# teensy_4_x100.net
KiCad netlist of a schematic drawn in EAGLE
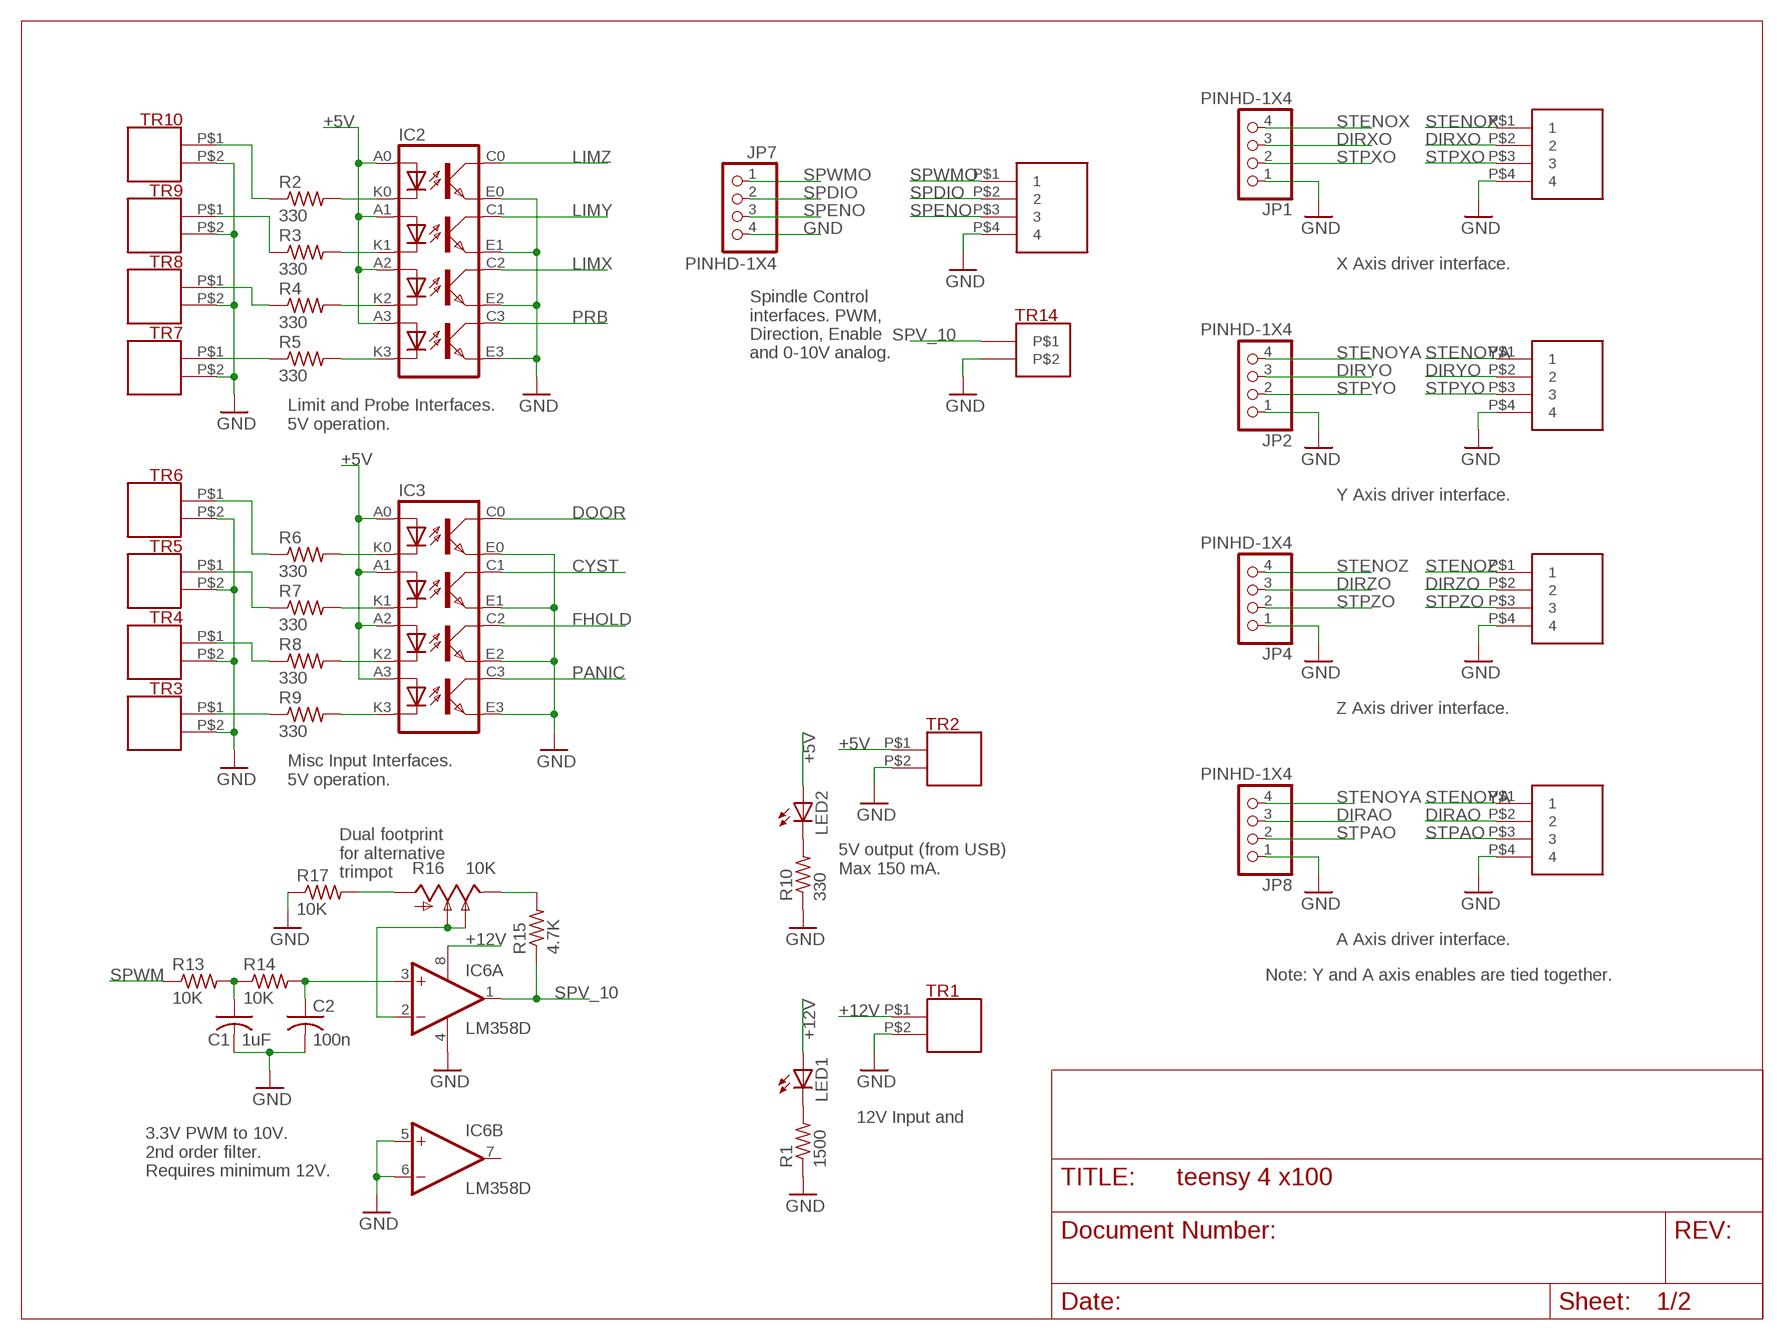
[diagram p0: schematic, sheet 1]
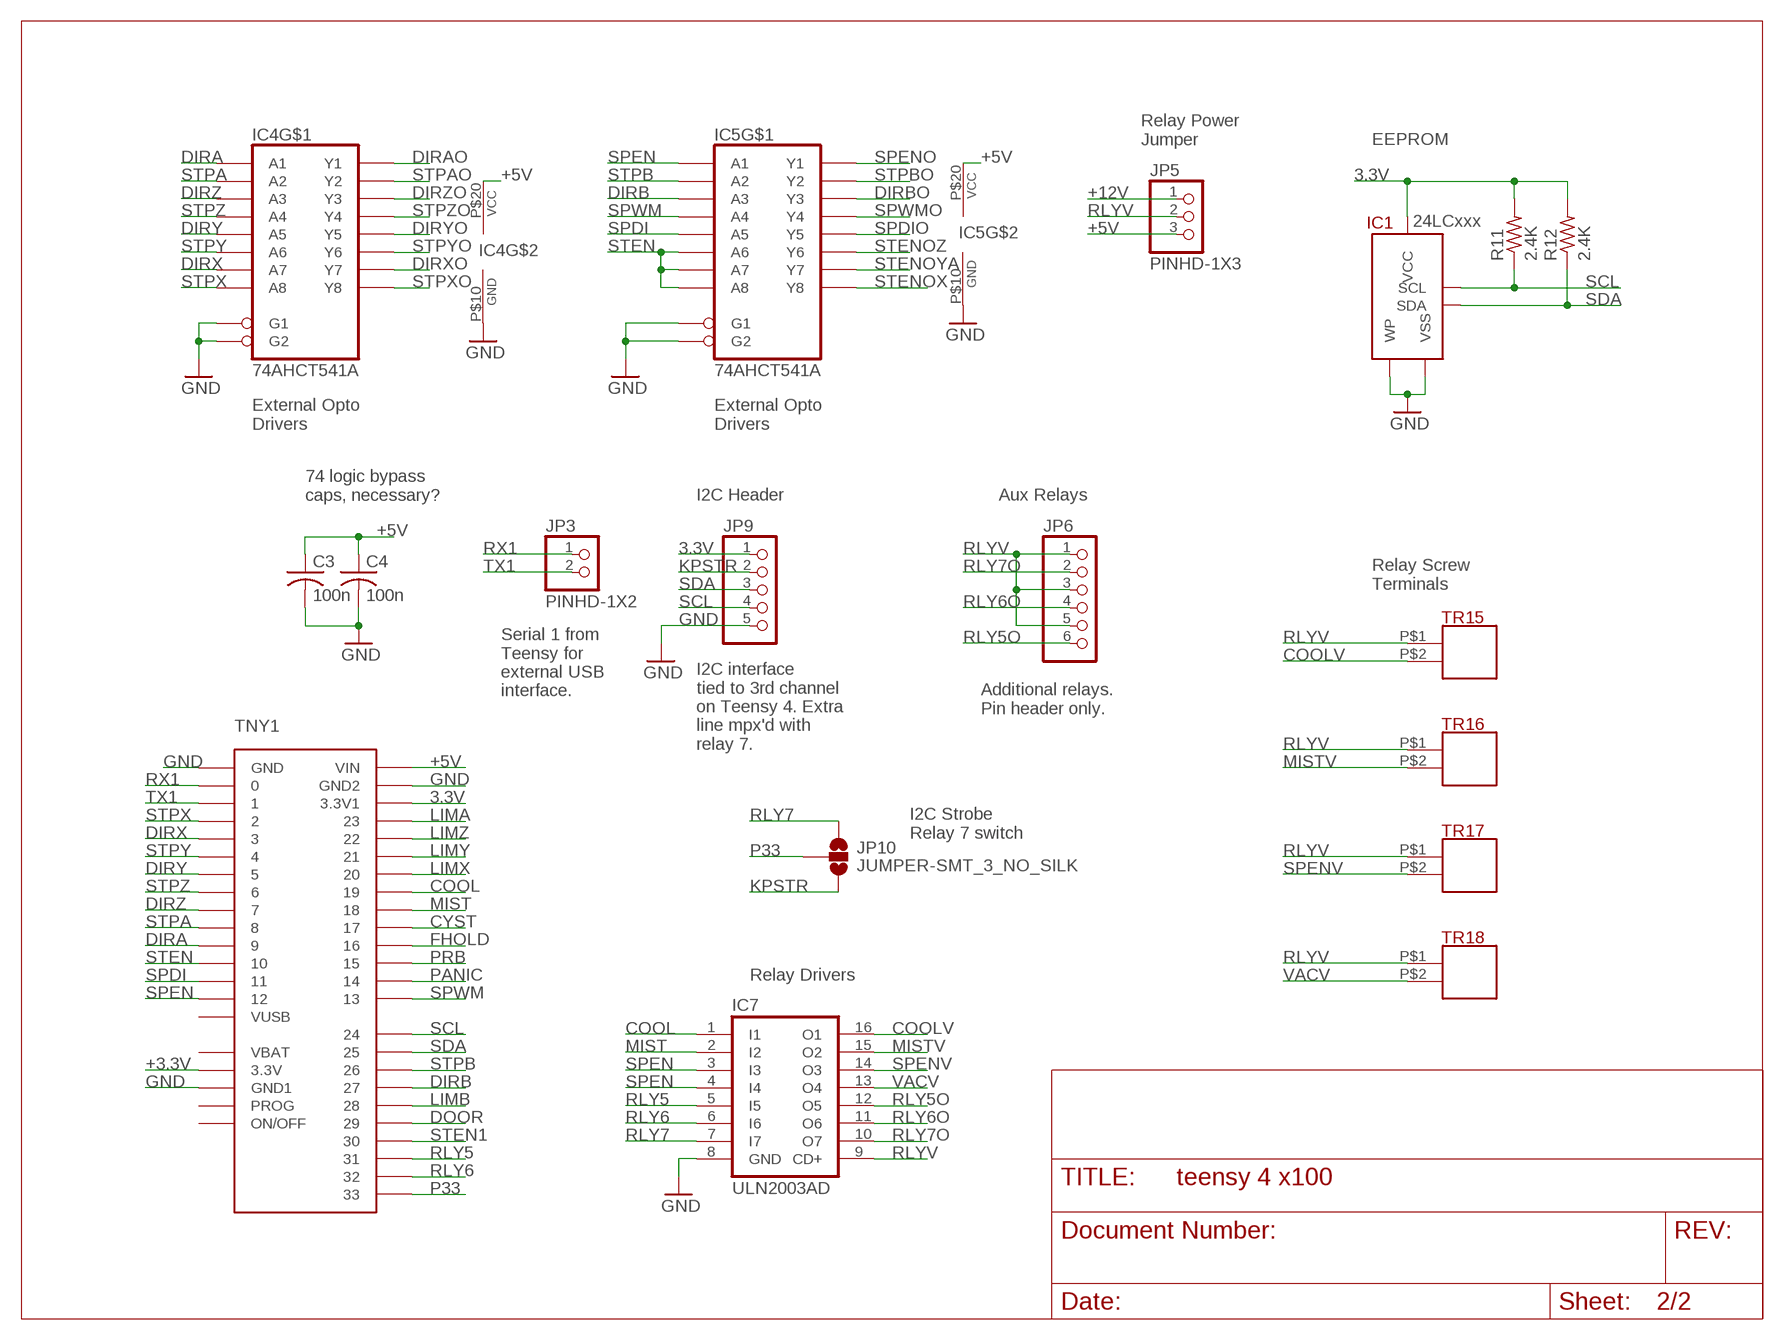
[diagram p1: schematic, sheet 2]

(export (version "E")
  (design (tool "Eeschema 10.0.6"))
  (components
    (comp (ref "C1")
      (value "1uF")
      (footprint "eagle-import:C1206")
      (libsource (lib "eagle-import") (part "C-USC1206"))
    )
    (comp (ref "C2")
      (value "100n")
      (footprint "eagle-import:C1206")
      (libsource (lib "eagle-import") (part "C-USC1206"))
    )
    (comp (ref "IC2")
      (value "LTV846S")
      (footprint "eagle-import:DIL16-SMD")
      (libsource (lib "eagle-import") (part "LVT846"))
    )
    (comp (ref "IC3")
      (value "LTV846S")
      (footprint "eagle-import:DIL16-SMD")
      (libsource (lib "eagle-import") (part "LVT846"))
    )
    (comp (ref "IC6")
      (value "LM358D")
      (footprint "eagle-import:SO08")
      (libsource (lib "eagle-import") (part "LM358D"))
    )
    (comp (ref "JP1")
      (value "PINHD-1X4")
      (footprint "eagle-import:1X04")
      (libsource (lib "eagle-import") (part "PINHD-1X4"))
    )
    (comp (ref "JP2")
      (value "PINHD-1X4")
      (footprint "eagle-import:1X04")
      (libsource (lib "eagle-import") (part "PINHD-1X4"))
    )
    (comp (ref "JP4")
      (value "PINHD-1X4")
      (footprint "eagle-import:1X04")
      (libsource (lib "eagle-import") (part "PINHD-1X4"))
    )
    (comp (ref "JP7")
      (value "PINHD-1X4")
      (footprint "eagle-import:1X04")
      (libsource (lib "eagle-import") (part "PINHD-1X4"))
    )
    (comp (ref "JP8")
      (value "PINHD-1X4")
      (footprint "eagle-import:1X04")
      (libsource (lib "eagle-import") (part "PINHD-1X4"))
    )
    (comp (ref "LED1")
      (value "LED3MM")
      (footprint "eagle-import:LED3MM")
      (libsource (lib "eagle-import") (part "LED3MM"))
    )
    (comp (ref "LED2")
      (value "LED3MM")
      (footprint "eagle-import:LED3MM")
      (libsource (lib "eagle-import") (part "LED3MM"))
    )
    (comp (ref "R1")
      (value "1500")
      (footprint "eagle-import:R1206")
      (libsource (lib "eagle-import") (part "R-US_R1206"))
    )
    (comp (ref "R2")
      (value "330")
      (footprint "eagle-import:R1206")
      (libsource (lib "eagle-import") (part "R-US_R1206"))
    )
    (comp (ref "R3")
      (value "330")
      (footprint "eagle-import:R1206")
      (libsource (lib "eagle-import") (part "R-US_R1206"))
    )
    (comp (ref "R4")
      (value "330")
      (footprint "eagle-import:R1206")
      (libsource (lib "eagle-import") (part "R-US_R1206"))
    )
    (comp (ref "R5")
      (value "330")
      (footprint "eagle-import:R1206")
      (libsource (lib "eagle-import") (part "R-US_R1206"))
    )
    (comp (ref "R6")
      (value "330")
      (footprint "eagle-import:R1206")
      (libsource (lib "eagle-import") (part "R-US_R1206"))
    )
    (comp (ref "R7")
      (value "330")
      (footprint "eagle-import:R1206")
      (libsource (lib "eagle-import") (part "R-US_R1206"))
    )
    (comp (ref "R8")
      (value "330")
      (footprint "eagle-import:R1206")
      (libsource (lib "eagle-import") (part "R-US_R1206"))
    )
    (comp (ref "R9")
      (value "330")
      (footprint "eagle-import:R1206")
      (libsource (lib "eagle-import") (part "R-US_R1206"))
    )
    (comp (ref "R10")
      (value "330")
      (footprint "eagle-import:R1206")
      (libsource (lib "eagle-import") (part "R-US_R1206"))
    )
    (comp (ref "R13")
      (value "10K")
      (footprint "eagle-import:R1206")
      (libsource (lib "eagle-import") (part "R-US_R1206"))
    )
    (comp (ref "R14")
      (value "10K")
      (footprint "eagle-import:R1206")
      (libsource (lib "eagle-import") (part "R-US_R1206"))
    )
    (comp (ref "R15")
      (value "4.7K")
      (footprint "eagle-import:R1206")
      (libsource (lib "eagle-import") (part "R-US_R1206"))
    )
    (comp (ref "R16")
      (value "10K")
      (footprint "eagle-import:B64Y")
      (libsource (lib "eagle-import") (part "TIMPOT_102"))
    )
    (comp (ref "R17")
      (value "10K")
      (footprint "eagle-import:R1206")
      (libsource (lib "eagle-import") (part "R-US_R1206"))
    )
    (comp (ref "TR1")
      (value "T35-2")
      (footprint "eagle-import:T35-2")
      (libsource (lib "eagle-import") (part "phils connectors_T35-2"))
    )
    (comp (ref "TR2")
      (value "T35-2")
      (footprint "eagle-import:T35-2")
      (libsource (lib "eagle-import") (part "phils connectors_T35-2"))
    )
    (comp (ref "TR3")
      (value "T35-2")
      (footprint "eagle-import:T35-2")
      (libsource (lib "eagle-import") (part "phils connectors_T35-2"))
    )
    (comp (ref "TR4")
      (value "T35-2")
      (footprint "eagle-import:T35-2")
      (libsource (lib "eagle-import") (part "phils connectors_T35-2"))
    )
    (comp (ref "TR5")
      (value "T35-2")
      (footprint "eagle-import:T35-2")
      (libsource (lib "eagle-import") (part "phils connectors_T35-2"))
    )
    (comp (ref "TR6")
      (value "T35-2")
      (footprint "eagle-import:T35-2")
      (libsource (lib "eagle-import") (part "phils connectors_T35-2"))
    )
    (comp (ref "TR7")
      (value "T35-2")
      (footprint "eagle-import:T35-2")
      (libsource (lib "eagle-import") (part "phils connectors_T35-2"))
    )
    (comp (ref "TR8")
      (value "T35-2")
      (footprint "eagle-import:T35-2")
      (libsource (lib "eagle-import") (part "phils connectors_T35-2"))
    )
    (comp (ref "TR9")
      (value "T35-2")
      (footprint "eagle-import:T35-2")
      (libsource (lib "eagle-import") (part "phils connectors_T35-2"))
    )
    (comp (ref "TR10")
      (value "T35-2")
      (footprint "eagle-import:T35-2")
      (libsource (lib "eagle-import") (part "phils connectors_T35-2"))
    )
    (comp (ref "TR11")
      (value "T35-4")
      (footprint "eagle-import:T35-4")
      (libsource (lib "eagle-import") (part "T35-4"))
    )
    (comp (ref "TR12")
      (value "T35-4")
      (footprint "eagle-import:T35-4")
      (libsource (lib "eagle-import") (part "T35-4"))
    )
    (comp (ref "TR13")
      (value "T35-4")
      (footprint "eagle-import:T35-4")
      (libsource (lib "eagle-import") (part "T35-4"))
    )
    (comp (ref "TR14")
      (value "T35-2")
      (footprint "eagle-import:T35-2")
      (libsource (lib "eagle-import") (part "T35-2"))
    )
    (comp (ref "TR19")
      (value "T35-4")
      (footprint "eagle-import:T35-4")
      (libsource (lib "eagle-import") (part "T35-4"))
    )
    (comp (ref "TR20")
      (value "T35-4")
      (footprint "eagle-import:T35-4")
      (libsource (lib "eagle-import") (part "T35-4"))
    )
    (comp (ref "C3")
      (value "100n")
      (footprint "eagle-import:C1206")
      (libsource (lib "eagle-import") (part "C-USC1206"))
    )
    (comp (ref "C4")
      (value "100n")
      (footprint "eagle-import:C1206")
      (libsource (lib "eagle-import") (part "C-USC1206"))
    )
    (comp (ref "IC1")
      (value "24LCxxx")
      (footprint "eagle-import:SOIC-8(MICROCHIP)")
      (libsource (lib "eagle-import") (part "24CWXXX"))
    )
    (comp (ref "IC4")
      (value "74AHCT541A")
      (footprint "eagle-import:TSSOP20")
      (libsource (lib "eagle-import") (part "74AHCT541A"))
    )
    (comp (ref "IC5")
      (value "74AHCT541A")
      (footprint "eagle-import:TSSOP20")
      (libsource (lib "eagle-import") (part "74AHCT541A"))
    )
    (comp (ref "IC7")
      (value "ULN2003AD")
      (footprint "eagle-import:SO16")
      (libsource (lib "eagle-import") (part "ULN2003AD"))
    )
    (comp (ref "JP3")
      (value "PINHD-1X2")
      (footprint "eagle-import:1X02")
      (libsource (lib "eagle-import") (part "PINHD-1X2"))
    )
    (comp (ref "JP5")
      (value "PINHD-1X3")
      (footprint "eagle-import:1X03")
      (libsource (lib "eagle-import") (part "PINHD-1X3"))
    )
    (comp (ref "JP6")
      (value "PINHD-1X6")
      (footprint "eagle-import:1X06")
      (libsource (lib "eagle-import") (part "PINHD-1X6"))
    )
    (comp (ref "JP9")
      (value "PINHD-1X5")
      (footprint "eagle-import:1X05")
      (libsource (lib "eagle-import") (part "PINHD-1X5"))
    )
    (comp (ref "JP10")
      (value "JUMPER-SMT_3_NO_SILK")
      (footprint "eagle-import:SMT-JUMPER_3_NO_SILK")
      (libsource (lib "eagle-import") (part "JUMPER-SMT_3_NO_SILK"))
    )
    (comp (ref "R11")
      (value "2.4K")
      (footprint "eagle-import:R1206")
      (libsource (lib "eagle-import") (part "R-US_R1206"))
    )
    (comp (ref "R12")
      (value "2.4K")
      (footprint "eagle-import:R1206")
      (libsource (lib "eagle-import") (part "R-US_R1206"))
    )
    (comp (ref "TNY1")
      (value "TEENSY4.0")
      (footprint "eagle-import:TEENSY4.0")
      (libsource (lib "eagle-import") (part "TEENSY4.0"))
    )
    (comp (ref "TR15")
      (value "T35-2")
      (footprint "eagle-import:T35-2")
      (libsource (lib "eagle-import") (part "phils connectors_T35-2"))
    )
    (comp (ref "TR16")
      (value "T35-2")
      (footprint "eagle-import:T35-2")
      (libsource (lib "eagle-import") (part "phils connectors_T35-2"))
    )
    (comp (ref "TR17")
      (value "T35-2")
      (footprint "eagle-import:T35-2")
      (libsource (lib "eagle-import") (part "phils connectors_T35-2"))
    )
    (comp (ref "TR18")
      (value "T35-2")
      (footprint "eagle-import:T35-2")
      (libsource (lib "eagle-import") (part "phils connectors_T35-2"))
    )
  )
  (nets
    (net (code "1") (name "+3.3V") (class "Default")
      (node (ref "TNY1") (pin "3.30") (pinfunction "3.3V_3.30") (pintype "bidirectional"))
    )
    (net (code "2") (name "+5V") (class "Default")
      (node (ref "C3") (pin "1") (pinfunction "1_1") (pintype "passive"))
      (node (ref "C4") (pin "1") (pinfunction "1_1") (pintype "passive"))
      (node (ref "IC2") (pin "A0") (pinfunction "A0_A0") (pintype "passive"))
      (node (ref "IC2") (pin "A1") (pinfunction "A1_A1") (pintype "passive"))
      (node (ref "IC2") (pin "A2") (pinfunction "A2_A2") (pintype "passive"))
      (node (ref "IC2") (pin "A3") (pinfunction "A3_A3") (pintype "passive"))
      (node (ref "IC3") (pin "A0") (pinfunction "A0_A0") (pintype "passive"))
      (node (ref "IC3") (pin "A1") (pinfunction "A1_A1") (pintype "passive"))
      (node (ref "IC3") (pin "A2") (pinfunction "A2_A2") (pintype "passive"))
      (node (ref "IC3") (pin "A3") (pinfunction "A3_A3") (pintype "passive"))
      (node (ref "IC4") (pin "P$20") (pinfunction "VCC_P$20") (pintype "power_in"))
      (node (ref "IC5") (pin "P$20") (pinfunction "VCC_P$20") (pintype "power_in"))
      (node (ref "JP5") (pin "3") (pinfunction "3_3") (pintype "passive"))
      (node (ref "LED2") (pin "A") (pinfunction "A_A") (pintype "passive"))
      (node (ref "TNY1") (pin "VIN") (pinfunction "VIN_VIN") (pintype "bidirectional"))
      (node (ref "TR2") (pin "P$1") (pinfunction "P$1_P$1") (pintype "bidirectional"))
    )
    (net (code "3") (name "+12V") (class "Default")
      (node (ref "IC6") (pin "8") (pinfunction "V+_8") (pintype "power_in"))
      (node (ref "JP5") (pin "1") (pinfunction "1_1") (pintype "passive"))
      (node (ref "LED1") (pin "A") (pinfunction "A_A") (pintype "passive"))
      (node (ref "TR1") (pin "P$1") (pinfunction "P$1_P$1") (pintype "bidirectional"))
    )
    (net (code "4") (name "3.3V") (class "Default")
      (node (ref "IC1") (pin "P$8") (pinfunction "VCC_P$8") (pintype "bidirectional"))
      (node (ref "JP9") (pin "1") (pinfunction "1_1") (pintype "passive"))
      (node (ref "R11") (pin "2") (pinfunction "2_2") (pintype "passive"))
      (node (ref "R12") (pin "2") (pinfunction "2_2") (pintype "passive"))
      (node (ref "TNY1") (pin "3.31") (pinfunction "3.3V1_3.31") (pintype "bidirectional"))
    )
    (net (code "5") (name "COOL") (class "Default")
      (node (ref "IC7") (pin "1") (pinfunction "I1_1") (pintype "input"))
      (node (ref "TNY1") (pin "19") (pinfunction "19_19") (pintype "bidirectional"))
    )
    (net (code "6") (name "COOLV") (class "Default")
      (node (ref "IC7") (pin "16") (pinfunction "O1_16") (pintype "open_collector"))
      (node (ref "TR15") (pin "P$2") (pinfunction "P$2_P$2") (pintype "bidirectional"))
    )
    (net (code "7") (name "CYST") (class "Default")
      (node (ref "IC3") (pin "C1") (pinfunction "COL1_C1") (pintype "passive"))
      (node (ref "TNY1") (pin "17") (pinfunction "17_17") (pintype "bidirectional"))
    )
    (net (code "8") (name "DIRA") (class "Default")
      (node (ref "IC4") (pin "P$2") (pinfunction "A1_P$2") (pintype "input"))
      (node (ref "TNY1") (pin "9") (pinfunction "9_9") (pintype "bidirectional"))
    )
    (net (code "9") (name "DIRAO") (class "Default")
      (node (ref "IC4") (pin "P$18") (pinfunction "Y1_P$18") (pintype "tri_state"))
      (node (ref "JP8") (pin "3") (pinfunction "3_3") (pintype "passive"))
      (node (ref "TR20") (pin "P$2") (pinfunction "2_P$2") (pintype "bidirectional"))
    )
    (net (code "10") (name "DIRB") (class "Default")
      (node (ref "IC5") (pin "P$4") (pinfunction "A3_P$4") (pintype "input"))
      (node (ref "TNY1") (pin "27") (pinfunction "27_27") (pintype "bidirectional"))
    )
    (net (code "11") (name "DIRBO") (class "Default")
      (node (ref "IC5") (pin "P$16") (pinfunction "Y3_P$16") (pintype "tri_state"))
    )
    (net (code "12") (name "DIRX") (class "Default")
      (node (ref "IC4") (pin "P$8") (pinfunction "A7_P$8") (pintype "input"))
      (node (ref "TNY1") (pin "3") (pinfunction "3_3") (pintype "bidirectional"))
    )
    (net (code "13") (name "DIRXO") (class "Default")
      (node (ref "IC4") (pin "P$12") (pinfunction "Y7_P$12") (pintype "tri_state"))
      (node (ref "JP1") (pin "3") (pinfunction "3_3") (pintype "passive"))
      (node (ref "TR11") (pin "P$2") (pinfunction "2_P$2") (pintype "bidirectional"))
    )
    (net (code "14") (name "DIRY") (class "Default")
      (node (ref "IC4") (pin "P$6") (pinfunction "A5_P$6") (pintype "input"))
      (node (ref "TNY1") (pin "5") (pinfunction "5_5") (pintype "bidirectional"))
    )
    (net (code "15") (name "DIRYO") (class "Default")
      (node (ref "IC4") (pin "P$14") (pinfunction "Y5_P$14") (pintype "tri_state"))
      (node (ref "JP2") (pin "3") (pinfunction "3_3") (pintype "passive"))
      (node (ref "TR12") (pin "P$2") (pinfunction "2_P$2") (pintype "bidirectional"))
    )
    (net (code "16") (name "DIRZ") (class "Default")
      (node (ref "IC4") (pin "P$4") (pinfunction "A3_P$4") (pintype "input"))
      (node (ref "TNY1") (pin "7") (pinfunction "7_7") (pintype "bidirectional"))
    )
    (net (code "17") (name "DIRZO") (class "Default")
      (node (ref "IC4") (pin "P$16") (pinfunction "Y3_P$16") (pintype "tri_state"))
      (node (ref "JP4") (pin "3") (pinfunction "3_3") (pintype "passive"))
      (node (ref "TR13") (pin "P$2") (pinfunction "2_P$2") (pintype "bidirectional"))
    )
    (net (code "18") (name "DOOR") (class "Default")
      (node (ref "IC3") (pin "C0") (pinfunction "COL0_C0") (pintype "passive"))
      (node (ref "TNY1") (pin "29") (pinfunction "29_29") (pintype "bidirectional"))
    )
    (net (code "19") (name "FHOLD") (class "Default")
      (node (ref "IC3") (pin "C2") (pinfunction "COL2_C2") (pintype "passive"))
      (node (ref "TNY1") (pin "16") (pinfunction "16_16") (pintype "bidirectional"))
    )
    (net (code "20") (name "GND") (class "Default")
      (node (ref "C1") (pin "2") (pinfunction "2_2") (pintype "passive"))
      (node (ref "C2") (pin "2") (pinfunction "2_2") (pintype "passive"))
      (node (ref "C3") (pin "2") (pinfunction "2_2") (pintype "passive"))
      (node (ref "C4") (pin "2") (pinfunction "2_2") (pintype "passive"))
      (node (ref "IC1") (pin "P$4") (pinfunction "VSS_P$4") (pintype "bidirectional"))
      (node (ref "IC1") (pin "P$7") (pinfunction "WP_P$7") (pintype "bidirectional"))
      (node (ref "IC2") (pin "E0") (pinfunction "EMIT0_E0") (pintype "passive"))
      (node (ref "IC2") (pin "E1") (pinfunction "EMIT1_E1") (pintype "passive"))
      (node (ref "IC2") (pin "E2") (pinfunction "EMIT2_E2") (pintype "passive"))
      (node (ref "IC2") (pin "E3") (pinfunction "EMIT3_E3") (pintype "passive"))
      (node (ref "IC3") (pin "E0") (pinfunction "EMIT0_E0") (pintype "passive"))
      (node (ref "IC3") (pin "E1") (pinfunction "EMIT1_E1") (pintype "passive"))
      (node (ref "IC3") (pin "E2") (pinfunction "EMIT2_E2") (pintype "passive"))
      (node (ref "IC3") (pin "E3") (pinfunction "EMIT3_E3") (pintype "passive"))
      (node (ref "IC4") (pin "P$1") (pinfunction "G1_P$1") (pintype "input"))
      (node (ref "IC4") (pin "P$10") (pinfunction "GND_P$10") (pintype "power_in"))
      (node (ref "IC4") (pin "P$19") (pinfunction "G2_P$19") (pintype "input"))
      (node (ref "IC5") (pin "P$1") (pinfunction "G1_P$1") (pintype "input"))
      (node (ref "IC5") (pin "P$10") (pinfunction "GND_P$10") (pintype "power_in"))
      (node (ref "IC5") (pin "P$19") (pinfunction "G2_P$19") (pintype "input"))
      (node (ref "IC6") (pin "4") (pinfunction "V-_4") (pintype "power_in"))
      (node (ref "IC6") (pin "5") (pinfunction "+IN_5") (pintype "input"))
      (node (ref "IC6") (pin "6") (pinfunction "-IN_6") (pintype "input"))
      (node (ref "IC7") (pin "8") (pinfunction "GND_8") (pintype "power_in"))
      (node (ref "JP1") (pin "1") (pinfunction "1_1") (pintype "passive"))
      (node (ref "JP2") (pin "1") (pinfunction "1_1") (pintype "passive"))
      (node (ref "JP4") (pin "1") (pinfunction "1_1") (pintype "passive"))
      (node (ref "JP7") (pin "4") (pinfunction "4_4") (pintype "passive"))
      (node (ref "JP8") (pin "1") (pinfunction "1_1") (pintype "passive"))
      (node (ref "JP9") (pin "5") (pinfunction "5_5") (pintype "passive"))
      (node (ref "R1") (pin "1") (pinfunction "1_1") (pintype "passive"))
      (node (ref "R10") (pin "1") (pinfunction "1_1") (pintype "passive"))
      (node (ref "R17") (pin "1") (pinfunction "1_1") (pintype "passive"))
      (node (ref "TNY1") (pin "GND") (pinfunction "GND_GND") (pintype "bidirectional"))
      (node (ref "TNY1") (pin "GND1") (pinfunction "GND1_GND1") (pintype "bidirectional"))
      (node (ref "TNY1") (pin "GND2") (pinfunction "GND2_GND2") (pintype "bidirectional"))
      (node (ref "TR1") (pin "P$2") (pinfunction "P$2_P$2") (pintype "bidirectional"))
      (node (ref "TR10") (pin "P$2") (pinfunction "P$2_P$2") (pintype "bidirectional"))
      (node (ref "TR11") (pin "P$4") (pinfunction "4_P$4") (pintype "bidirectional"))
      (node (ref "TR12") (pin "P$4") (pinfunction "4_P$4") (pintype "bidirectional"))
      (node (ref "TR13") (pin "P$4") (pinfunction "4_P$4") (pintype "bidirectional"))
      (node (ref "TR14") (pin "P$2") (pinfunction "P$2_P$2") (pintype "bidirectional"))
      (node (ref "TR19") (pin "P$4") (pinfunction "4_P$4") (pintype "bidirectional"))
      (node (ref "TR2") (pin "P$2") (pinfunction "P$2_P$2") (pintype "bidirectional"))
      (node (ref "TR20") (pin "P$4") (pinfunction "4_P$4") (pintype "bidirectional"))
      (node (ref "TR3") (pin "P$2") (pinfunction "P$2_P$2") (pintype "bidirectional"))
      (node (ref "TR4") (pin "P$2") (pinfunction "P$2_P$2") (pintype "bidirectional"))
      (node (ref "TR5") (pin "P$2") (pinfunction "P$2_P$2") (pintype "bidirectional"))
      (node (ref "TR6") (pin "P$2") (pinfunction "P$2_P$2") (pintype "bidirectional"))
      (node (ref "TR7") (pin "P$2") (pinfunction "P$2_P$2") (pintype "bidirectional"))
      (node (ref "TR8") (pin "P$2") (pinfunction "P$2_P$2") (pintype "bidirectional"))
      (node (ref "TR9") (pin "P$2") (pinfunction "P$2_P$2") (pintype "bidirectional"))
    )
    (net (code "21") (name "KPSTR") (class "Default")
      (node (ref "JP10") (pin "3") (pinfunction "3_3") (pintype "passive"))
      (node (ref "JP9") (pin "2") (pinfunction "2_2") (pintype "passive"))
    )
    (net (code "22") (name "LIMA") (class "Default")
      (node (ref "TNY1") (pin "23") (pinfunction "23_23") (pintype "bidirectional"))
    )
    (net (code "23") (name "LIMB") (class "Default")
      (node (ref "TNY1") (pin "28") (pinfunction "28_28") (pintype "bidirectional"))
    )
    (net (code "24") (name "LIMX") (class "Default")
      (node (ref "IC2") (pin "C2") (pinfunction "COL2_C2") (pintype "passive"))
      (node (ref "TNY1") (pin "20") (pinfunction "20_20") (pintype "bidirectional"))
    )
    (net (code "25") (name "LIMY") (class "Default")
      (node (ref "IC2") (pin "C1") (pinfunction "COL1_C1") (pintype "passive"))
      (node (ref "TNY1") (pin "21") (pinfunction "21_21") (pintype "bidirectional"))
    )
    (net (code "26") (name "LIMZ") (class "Default")
      (node (ref "IC2") (pin "C0") (pinfunction "COL0_C0") (pintype "passive"))
      (node (ref "TNY1") (pin "22") (pinfunction "22_22") (pintype "bidirectional"))
    )
    (net (code "27") (name "MIST") (class "Default")
      (node (ref "IC7") (pin "2") (pinfunction "I2_2") (pintype "input"))
      (node (ref "TNY1") (pin "18") (pinfunction "18_18") (pintype "bidirectional"))
    )
    (net (code "28") (name "MISTV") (class "Default")
      (node (ref "IC7") (pin "15") (pinfunction "O2_15") (pintype "open_collector"))
      (node (ref "TR16") (pin "P$2") (pinfunction "P$2_P$2") (pintype "bidirectional"))
    )
    (net (code "29") (name "Net-(C1-Pad1)") (class "Default")
      (node (ref "C1") (pin "1") (pinfunction "1_1") (pintype "passive"))
      (node (ref "R13") (pin "2") (pinfunction "2_2") (pintype "passive"))
      (node (ref "R14") (pin "1") (pinfunction "1_1") (pintype "passive"))
    )
    (net (code "30") (name "Net-(IC2-C0)") (class "Default")
      (node (ref "IC2") (pin "K0") (pinfunction "C0_K0") (pintype "passive"))
      (node (ref "R2") (pin "2") (pinfunction "2_2") (pintype "passive"))
    )
    (net (code "31") (name "Net-(IC2-C1)") (class "Default")
      (node (ref "IC2") (pin "K1") (pinfunction "C1_K1") (pintype "passive"))
      (node (ref "R3") (pin "2") (pinfunction "2_2") (pintype "passive"))
    )
    (net (code "32") (name "Net-(IC2-C2)") (class "Default")
      (node (ref "IC2") (pin "K2") (pinfunction "C2_K2") (pintype "passive"))
      (node (ref "R4") (pin "2") (pinfunction "2_2") (pintype "passive"))
    )
    (net (code "33") (name "Net-(IC2-C3)") (class "Default")
      (node (ref "IC2") (pin "K3") (pinfunction "C3_K3") (pintype "passive"))
      (node (ref "R5") (pin "2") (pinfunction "2_2") (pintype "passive"))
    )
    (net (code "34") (name "Net-(IC3-C0)") (class "Default")
      (node (ref "IC3") (pin "K0") (pinfunction "C0_K0") (pintype "passive"))
      (node (ref "R6") (pin "2") (pinfunction "2_2") (pintype "passive"))
    )
    (net (code "35") (name "Net-(IC3-C1)") (class "Default")
      (node (ref "IC3") (pin "K1") (pinfunction "C1_K1") (pintype "passive"))
      (node (ref "R7") (pin "2") (pinfunction "2_2") (pintype "passive"))
    )
    (net (code "36") (name "Net-(IC3-C2)") (class "Default")
      (node (ref "IC3") (pin "K2") (pinfunction "C2_K2") (pintype "passive"))
      (node (ref "R8") (pin "2") (pinfunction "2_2") (pintype "passive"))
    )
    (net (code "37") (name "Net-(IC3-C3)") (class "Default")
      (node (ref "IC3") (pin "K3") (pinfunction "C3_K3") (pintype "passive"))
      (node (ref "R9") (pin "2") (pinfunction "2_2") (pintype "passive"))
    )
    (net (code "38") (name "Net-(IC6A-+IN)") (class "Default")
      (node (ref "C2") (pin "1") (pinfunction "1_1") (pintype "passive"))
      (node (ref "IC6") (pin "3") (pinfunction "+IN_3") (pintype "input"))
      (node (ref "R14") (pin "2") (pinfunction "2_2") (pintype "passive"))
    )
    (net (code "39") (name "Net-(IC6A--IN)") (class "Default")
      (node (ref "IC6") (pin "2") (pinfunction "-IN_2") (pintype "input"))
      (node (ref "R16") (pin "S") (pinfunction "S_S") (pintype "passive"))
      (node (ref "R16") (pin "S1") (pinfunction "S1_S1") (pintype "passive"))
    )
    (net (code "40") (name "Net-(LED1-C)") (class "Default")
      (node (ref "LED1") (pin "K") (pinfunction "C_K") (pintype "passive"))
      (node (ref "R1") (pin "2") (pinfunction "2_2") (pintype "passive"))
    )
    (net (code "41") (name "Net-(LED2-C)") (class "Default")
      (node (ref "LED2") (pin "K") (pinfunction "C_K") (pintype "passive"))
      (node (ref "R10") (pin "2") (pinfunction "2_2") (pintype "passive"))
    )
    (net (code "42") (name "Net-(R2-Pad1)") (class "Default")
      (node (ref "R2") (pin "1") (pinfunction "1_1") (pintype "passive"))
      (node (ref "TR10") (pin "P$1") (pinfunction "P$1_P$1") (pintype "bidirectional"))
    )
    (net (code "43") (name "Net-(R3-Pad1)") (class "Default")
      (node (ref "R3") (pin "1") (pinfunction "1_1") (pintype "passive"))
      (node (ref "TR9") (pin "P$1") (pinfunction "P$1_P$1") (pintype "bidirectional"))
    )
    (net (code "44") (name "Net-(R4-Pad1)") (class "Default")
      (node (ref "R4") (pin "1") (pinfunction "1_1") (pintype "passive"))
      (node (ref "TR8") (pin "P$1") (pinfunction "P$1_P$1") (pintype "bidirectional"))
    )
    (net (code "45") (name "Net-(R5-Pad1)") (class "Default")
      (node (ref "R5") (pin "1") (pinfunction "1_1") (pintype "passive"))
      (node (ref "TR7") (pin "P$1") (pinfunction "P$1_P$1") (pintype "bidirectional"))
    )
    (net (code "46") (name "Net-(R6-Pad1)") (class "Default")
      (node (ref "R6") (pin "1") (pinfunction "1_1") (pintype "passive"))
      (node (ref "TR6") (pin "P$1") (pinfunction "P$1_P$1") (pintype "bidirectional"))
    )
    (net (code "47") (name "Net-(R7-Pad1)") (class "Default")
      (node (ref "R7") (pin "1") (pinfunction "1_1") (pintype "passive"))
      (node (ref "TR5") (pin "P$1") (pinfunction "P$1_P$1") (pintype "bidirectional"))
    )
    (net (code "48") (name "Net-(R8-Pad1)") (class "Default")
      (node (ref "R8") (pin "1") (pinfunction "1_1") (pintype "passive"))
      (node (ref "TR4") (pin "P$1") (pinfunction "P$1_P$1") (pintype "bidirectional"))
    )
    (net (code "49") (name "Net-(R9-Pad1)") (class "Default")
      (node (ref "R9") (pin "1") (pinfunction "1_1") (pintype "passive"))
      (node (ref "TR3") (pin "P$1") (pinfunction "P$1_P$1") (pintype "bidirectional"))
    )
    (net (code "50") (name "Net-(R15-Pad2)") (class "Default")
      (node (ref "R15") (pin "2") (pinfunction "2_2") (pintype "passive"))
      (node (ref "R16") (pin "E") (pinfunction "E_E") (pintype "passive"))
    )
    (net (code "51") (name "Net-(R16-PadA)") (class "Default")
      (node (ref "R16") (pin "A") (pinfunction "A_A") (pintype "passive"))
      (node (ref "R17") (pin "2") (pinfunction "2_2") (pintype "passive"))
    )
    (net (code "52") (name "P33") (class "Default")
      (node (ref "JP10") (pin "2") (pinfunction "2_2") (pintype "passive"))
      (node (ref "TNY1") (pin "33") (pinfunction "33_33") (pintype "bidirectional"))
    )
    (net (code "53") (name "PANIC") (class "Default")
      (node (ref "IC3") (pin "C3") (pinfunction "COL3_C3") (pintype "passive"))
      (node (ref "TNY1") (pin "14") (pinfunction "14_14") (pintype "bidirectional"))
    )
    (net (code "54") (name "PRB") (class "Default")
      (node (ref "IC2") (pin "C3") (pinfunction "COL3_C3") (pintype "passive"))
      (node (ref "TNY1") (pin "15") (pinfunction "15_15") (pintype "bidirectional"))
    )
    (net (code "55") (name "RLY5") (class "Default")
      (node (ref "IC7") (pin "5") (pinfunction "I5_5") (pintype "input"))
      (node (ref "TNY1") (pin "31") (pinfunction "31_31") (pintype "bidirectional"))
    )
    (net (code "56") (name "RLY5O") (class "Default")
      (node (ref "IC7") (pin "12") (pinfunction "O5_12") (pintype "open_collector"))
      (node (ref "JP6") (pin "6") (pinfunction "6_6") (pintype "passive"))
    )
    (net (code "57") (name "RLY6") (class "Default")
      (node (ref "IC7") (pin "6") (pinfunction "I6_6") (pintype "input"))
      (node (ref "TNY1") (pin "32") (pinfunction "32_32") (pintype "bidirectional"))
    )
    (net (code "58") (name "RLY6O") (class "Default")
      (node (ref "IC7") (pin "11") (pinfunction "O6_11") (pintype "open_collector"))
      (node (ref "JP6") (pin "4") (pinfunction "4_4") (pintype "passive"))
    )
    (net (code "59") (name "RLY7") (class "Default")
      (node (ref "IC7") (pin "7") (pinfunction "I7_7") (pintype "input"))
      (node (ref "JP10") (pin "1") (pinfunction "1_1") (pintype "passive"))
    )
    (net (code "60") (name "RLY7O") (class "Default")
      (node (ref "IC7") (pin "10") (pinfunction "O7_10") (pintype "open_collector"))
      (node (ref "JP6") (pin "2") (pinfunction "2_2") (pintype "passive"))
    )
    (net (code "61") (name "RLYV") (class "Default")
      (node (ref "IC7") (pin "9") (pinfunction "CD+_9") (pintype "passive"))
      (node (ref "JP5") (pin "2") (pinfunction "2_2") (pintype "passive"))
      (node (ref "JP6") (pin "1") (pinfunction "1_1") (pintype "passive"))
      (node (ref "JP6") (pin "3") (pinfunction "3_3") (pintype "passive"))
      (node (ref "JP6") (pin "5") (pinfunction "5_5") (pintype "passive"))
      (node (ref "TR15") (pin "P$1") (pinfunction "P$1_P$1") (pintype "bidirectional"))
      (node (ref "TR16") (pin "P$1") (pinfunction "P$1_P$1") (pintype "bidirectional"))
      (node (ref "TR17") (pin "P$1") (pinfunction "P$1_P$1") (pintype "bidirectional"))
      (node (ref "TR18") (pin "P$1") (pinfunction "P$1_P$1") (pintype "bidirectional"))
    )
    (net (code "62") (name "RX1") (class "Default")
      (node (ref "JP3") (pin "1") (pinfunction "1_1") (pintype "passive"))
      (node (ref "TNY1") (pin "0") (pinfunction "0_0") (pintype "bidirectional"))
    )
    (net (code "63") (name "SCL") (class "Default")
      (node (ref "IC1") (pin "P$6") (pinfunction "SCL_P$6") (pintype "bidirectional"))
      (node (ref "JP9") (pin "4") (pinfunction "4_4") (pintype "passive"))
      (node (ref "R11") (pin "1") (pinfunction "1_1") (pintype "passive"))
      (node (ref "TNY1") (pin "24") (pinfunction "24_24") (pintype "bidirectional"))
    )
    (net (code "64") (name "SDA") (class "Default")
      (node (ref "IC1") (pin "P$5") (pinfunction "SDA_P$5") (pintype "bidirectional"))
      (node (ref "JP9") (pin "3") (pinfunction "3_3") (pintype "passive"))
      (node (ref "R12") (pin "1") (pinfunction "1_1") (pintype "passive"))
      (node (ref "TNY1") (pin "25") (pinfunction "25_25") (pintype "bidirectional"))
    )
    (net (code "65") (name "SPDI") (class "Default")
      (node (ref "IC5") (pin "P$6") (pinfunction "A5_P$6") (pintype "input"))
      (node (ref "TNY1") (pin "11") (pinfunction "11_11") (pintype "bidirectional"))
    )
    (net (code "66") (name "SPDIO") (class "Default")
      (node (ref "IC5") (pin "P$14") (pinfunction "Y5_P$14") (pintype "tri_state"))
      (node (ref "JP7") (pin "2") (pinfunction "2_2") (pintype "passive"))
      (node (ref "TR19") (pin "P$2") (pinfunction "2_P$2") (pintype "bidirectional"))
    )
    (net (code "67") (name "SPEN") (class "Default")
      (node (ref "IC5") (pin "P$2") (pinfunction "A1_P$2") (pintype "input"))
      (node (ref "IC7") (pin "3") (pinfunction "I3_3") (pintype "input"))
      (node (ref "IC7") (pin "4") (pinfunction "I4_4") (pintype "input"))
      (node (ref "TNY1") (pin "12") (pinfunction "12_12") (pintype "bidirectional"))
    )
    (net (code "68") (name "SPENO") (class "Default")
      (node (ref "IC5") (pin "P$18") (pinfunction "Y1_P$18") (pintype "tri_state"))
      (node (ref "JP7") (pin "3") (pinfunction "3_3") (pintype "passive"))
      (node (ref "TR19") (pin "P$3") (pinfunction "3_P$3") (pintype "bidirectional"))
    )
    (net (code "69") (name "SPENV") (class "Default")
      (node (ref "IC7") (pin "14") (pinfunction "O3_14") (pintype "open_collector"))
      (node (ref "TR17") (pin "P$2") (pinfunction "P$2_P$2") (pintype "bidirectional"))
    )
    (net (code "70") (name "SPV_10") (class "Default")
      (node (ref "IC6") (pin "1") (pinfunction "OUT_1") (pintype "output"))
      (node (ref "R15") (pin "1") (pinfunction "1_1") (pintype "passive"))
      (node (ref "TR14") (pin "P$1") (pinfunction "P$1_P$1") (pintype "bidirectional"))
    )
    (net (code "71") (name "SPWM") (class "Default")
      (node (ref "IC5") (pin "P$5") (pinfunction "A4_P$5") (pintype "input"))
      (node (ref "R13") (pin "1") (pinfunction "1_1") (pintype "passive"))
      (node (ref "TNY1") (pin "13") (pinfunction "13_13") (pintype "bidirectional"))
    )
    (net (code "72") (name "SPWMO") (class "Default")
      (node (ref "IC5") (pin "P$15") (pinfunction "Y4_P$15") (pintype "tri_state"))
      (node (ref "JP7") (pin "1") (pinfunction "1_1") (pintype "passive"))
      (node (ref "TR19") (pin "P$1") (pinfunction "1_P$1") (pintype "bidirectional"))
    )
    (net (code "73") (name "STEN") (class "Default")
      (node (ref "IC5") (pin "P$7") (pinfunction "A6_P$7") (pintype "input"))
      (node (ref "IC5") (pin "P$8") (pinfunction "A7_P$8") (pintype "input"))
      (node (ref "IC5") (pin "P$9") (pinfunction "A8_P$9") (pintype "input"))
      (node (ref "TNY1") (pin "10") (pinfunction "10_10") (pintype "bidirectional"))
    )
    (net (code "74") (name "STEN1") (class "Default")
      (node (ref "TNY1") (pin "30") (pinfunction "30_30") (pintype "bidirectional"))
    )
    (net (code "75") (name "STENOX") (class "Default")
      (node (ref "IC5") (pin "P$11") (pinfunction "Y8_P$11") (pintype "tri_state"))
      (node (ref "JP1") (pin "4") (pinfunction "4_4") (pintype "passive"))
      (node (ref "TR11") (pin "P$1") (pinfunction "1_P$1") (pintype "bidirectional"))
    )
    (net (code "76") (name "STENOYA") (class "Default")
      (node (ref "IC5") (pin "P$12") (pinfunction "Y7_P$12") (pintype "tri_state"))
      (node (ref "JP2") (pin "4") (pinfunction "4_4") (pintype "passive"))
      (node (ref "JP8") (pin "4") (pinfunction "4_4") (pintype "passive"))
      (node (ref "TR12") (pin "P$1") (pinfunction "1_P$1") (pintype "bidirectional"))
      (node (ref "TR20") (pin "P$1") (pinfunction "1_P$1") (pintype "bidirectional"))
    )
    (net (code "77") (name "STENOZ") (class "Default")
      (node (ref "IC5") (pin "P$13") (pinfunction "Y6_P$13") (pintype "tri_state"))
      (node (ref "JP4") (pin "4") (pinfunction "4_4") (pintype "passive"))
      (node (ref "TR13") (pin "P$1") (pinfunction "1_P$1") (pintype "bidirectional"))
    )
    (net (code "78") (name "STPA") (class "Default")
      (node (ref "IC4") (pin "P$3") (pinfunction "A2_P$3") (pintype "input"))
      (node (ref "TNY1") (pin "8") (pinfunction "8_8") (pintype "bidirectional"))
    )
    (net (code "79") (name "STPAO") (class "Default")
      (node (ref "IC4") (pin "P$17") (pinfunction "Y2_P$17") (pintype "tri_state"))
      (node (ref "JP8") (pin "2") (pinfunction "2_2") (pintype "passive"))
      (node (ref "TR20") (pin "P$3") (pinfunction "3_P$3") (pintype "bidirectional"))
    )
    (net (code "80") (name "STPB") (class "Default")
      (node (ref "IC5") (pin "P$3") (pinfunction "A2_P$3") (pintype "input"))
      (node (ref "TNY1") (pin "26") (pinfunction "26_26") (pintype "bidirectional"))
    )
    (net (code "81") (name "STPBO") (class "Default")
      (node (ref "IC5") (pin "P$17") (pinfunction "Y2_P$17") (pintype "tri_state"))
    )
    (net (code "82") (name "STPX") (class "Default")
      (node (ref "IC4") (pin "P$9") (pinfunction "A8_P$9") (pintype "input"))
      (node (ref "TNY1") (pin "2") (pinfunction "2_2") (pintype "bidirectional"))
    )
    (net (code "83") (name "STPXO") (class "Default")
      (node (ref "IC4") (pin "P$11") (pinfunction "Y8_P$11") (pintype "tri_state"))
      (node (ref "JP1") (pin "2") (pinfunction "2_2") (pintype "passive"))
      (node (ref "TR11") (pin "P$3") (pinfunction "3_P$3") (pintype "bidirectional"))
    )
    (net (code "84") (name "STPY") (class "Default")
      (node (ref "IC4") (pin "P$7") (pinfunction "A6_P$7") (pintype "input"))
      (node (ref "TNY1") (pin "4") (pinfunction "4_4") (pintype "bidirectional"))
    )
    (net (code "85") (name "STPYO") (class "Default")
      (node (ref "IC4") (pin "P$13") (pinfunction "Y6_P$13") (pintype "tri_state"))
      (node (ref "JP2") (pin "2") (pinfunction "2_2") (pintype "passive"))
      (node (ref "TR12") (pin "P$3") (pinfunction "3_P$3") (pintype "bidirectional"))
    )
    (net (code "86") (name "STPZ") (class "Default")
      (node (ref "IC4") (pin "P$5") (pinfunction "A4_P$5") (pintype "input"))
      (node (ref "TNY1") (pin "6") (pinfunction "6_6") (pintype "bidirectional"))
    )
    (net (code "87") (name "STPZO") (class "Default")
      (node (ref "IC4") (pin "P$15") (pinfunction "Y4_P$15") (pintype "tri_state"))
      (node (ref "JP4") (pin "2") (pinfunction "2_2") (pintype "passive"))
      (node (ref "TR13") (pin "P$3") (pinfunction "3_P$3") (pintype "bidirectional"))
    )
    (net (code "88") (name "TX1") (class "Default")
      (node (ref "JP3") (pin "2") (pinfunction "2_2") (pintype "passive"))
      (node (ref "TNY1") (pin "1") (pinfunction "1_1") (pintype "bidirectional"))
    )
    (net (code "89") (name "VACV") (class "Default")
      (node (ref "IC7") (pin "13") (pinfunction "O4_13") (pintype "open_collector"))
      (node (ref "TR18") (pin "P$2") (pinfunction "P$2_P$2") (pintype "bidirectional"))
    )
    (net (code "90") (name "unconnected-(IC6B-OUT-Pad7)") (class "Default")
      (node (ref "IC6") (pin "7") (pinfunction "OUT_7") (pintype "output"))
    )
    (net (code "91") (name "unconnected-(TNY1-PadON{slash}OFF)") (class "Default")
      (node (ref "TNY1") (pin "ON/OFF") (pinfunction "ON/OFF_ON/OFF") (pintype "bidirectional"))
    )
    (net (code "92") (name "unconnected-(TNY1-PadPROG)") (class "Default")
      (node (ref "TNY1") (pin "PROG") (pinfunction "PROG_PROG") (pintype "bidirectional"))
    )
    (net (code "93") (name "unconnected-(TNY1-PadVBAT)") (class "Default")
      (node (ref "TNY1") (pin "VBAT") (pinfunction "VBAT_VBAT") (pintype "bidirectional"))
    )
    (net (code "94") (name "unconnected-(TNY1-PadVUSB)") (class "Default")
      (node (ref "TNY1") (pin "VUSB") (pinfunction "VUSB_VUSB") (pintype "bidirectional"))
    )
  )
)
